# Isolator_SPWM.net
KiCad netlist of a schematic drawn in Altium Designer
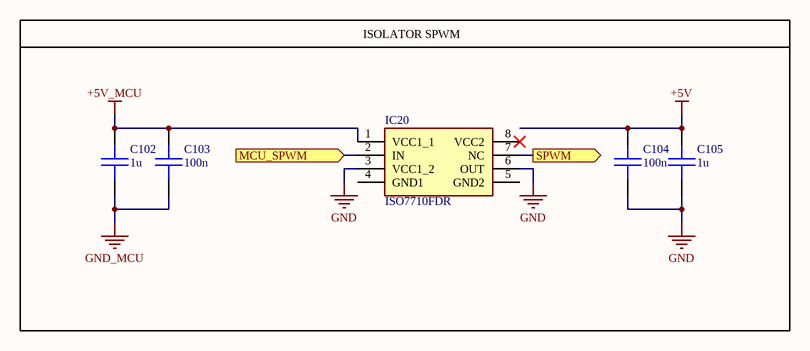
[diagram p0: Isolator_SPWM.SchDoc]

(export (version "E")
  (design (tool "Eeschema 10.0.6"))
  (components
    (comp (ref "C102")
      (value "1u")
      (footprint "C_0603")
      (description "SMD Chip Capacitor")
      (libsource (lib "My_Integrated_Lib") (part "CAP"))
    )
    (comp (ref "C103")
      (value "100n")
      (footprint "C_0603")
      (description "SMD Chip Capacitor")
      (libsource (lib "My_Integrated_Lib") (part "CAP"))
    )
    (comp (ref "C104")
      (value "100n")
      (footprint "C_0603")
      (description "SMD Chip Capacitor")
      (libsource (lib "My_Integrated_Lib") (part "CAP"))
    )
    (comp (ref "C105")
      (value "1u")
      (footprint "C_0603")
      (description "SMD Chip Capacitor")
      (libsource (lib "My_Integrated_Lib") (part "CAP"))
    )
    (comp (ref "IC20")
      (value "ISO7710FDR")
      (footprint "SOIC127P600X175-8N")
      (description "Integrated Circuit")
      (fields (field (name "MOUSER PART NUMBER") "595-ISO7710FDR"))
      (libsource (lib "My_Integrated_Lib") (part "ISO7710FDR"))
    )
  )
  (nets
    (net (code "1") (name "+5V") (class "Default")
      (node (ref "C104") (pin "2") (pinfunction "2_2") (pintype "passive"))
      (node (ref "C105") (pin "2") (pinfunction "2_2") (pintype "passive"))
    )
    (net (code "2") (name "+5V_MCU") (class "Default")
      (node (ref "C102") (pin "2") (pinfunction "2_2") (pintype "passive"))
      (node (ref "C103") (pin "2") (pinfunction "2_2") (pintype "passive"))
      (node (ref "IC20") (pin "1") (pinfunction "VCC1_1_1") (pintype "passive"))
    )
    (net (code "3") (name "/MCU_SPWM") (class "Default")
      (node (ref "IC20") (pin "2") (pinfunction "IN_2") (pintype "passive"))
    )
    (net (code "4") (name "/SPWM") (class "Default")
      (node (ref "IC20") (pin "7") (pinfunction "NC_7") (pintype "passive"))
    )
    (net (code "5") (name "GND") (class "Default")
      (node (ref "C104") (pin "1") (pinfunction "1_1") (pintype "passive"))
      (node (ref "C105") (pin "1") (pinfunction "1_1") (pintype "passive"))
      (node (ref "IC20") (pin "3") (pinfunction "VCC1_2_3") (pintype "passive"))
      (node (ref "IC20") (pin "6") (pinfunction "OUT_6") (pintype "passive"))
    )
    (net (code "6") (name "GND_MCU") (class "Default")
      (node (ref "C102") (pin "1") (pinfunction "1_1") (pintype "passive"))
      (node (ref "C103") (pin "1") (pinfunction "1_1") (pintype "passive"))
    )
    (net (code "7") (name "unconnected-(IC20-GND1-Pad4)") (class "Default")
      (node (ref "IC20") (pin "4") (pinfunction "GND1_4") (pintype "passive"))
    )
    (net (code "8") (name "unconnected-(IC20-GND2-Pad5)") (class "Default")
      (node (ref "IC20") (pin "5") (pinfunction "GND2_5") (pintype "passive"))
    )
    (net (code "9") (name "unconnected-(IC20-VCC2-Pad8)") (class "Default")
      (node (ref "IC20") (pin "8") (pinfunction "VCC2_8") (pintype "passive+no_connect"))
    )
  )
)
